# gluecksrad.net
KiCad netlist of a schematic drawn in EAGLE
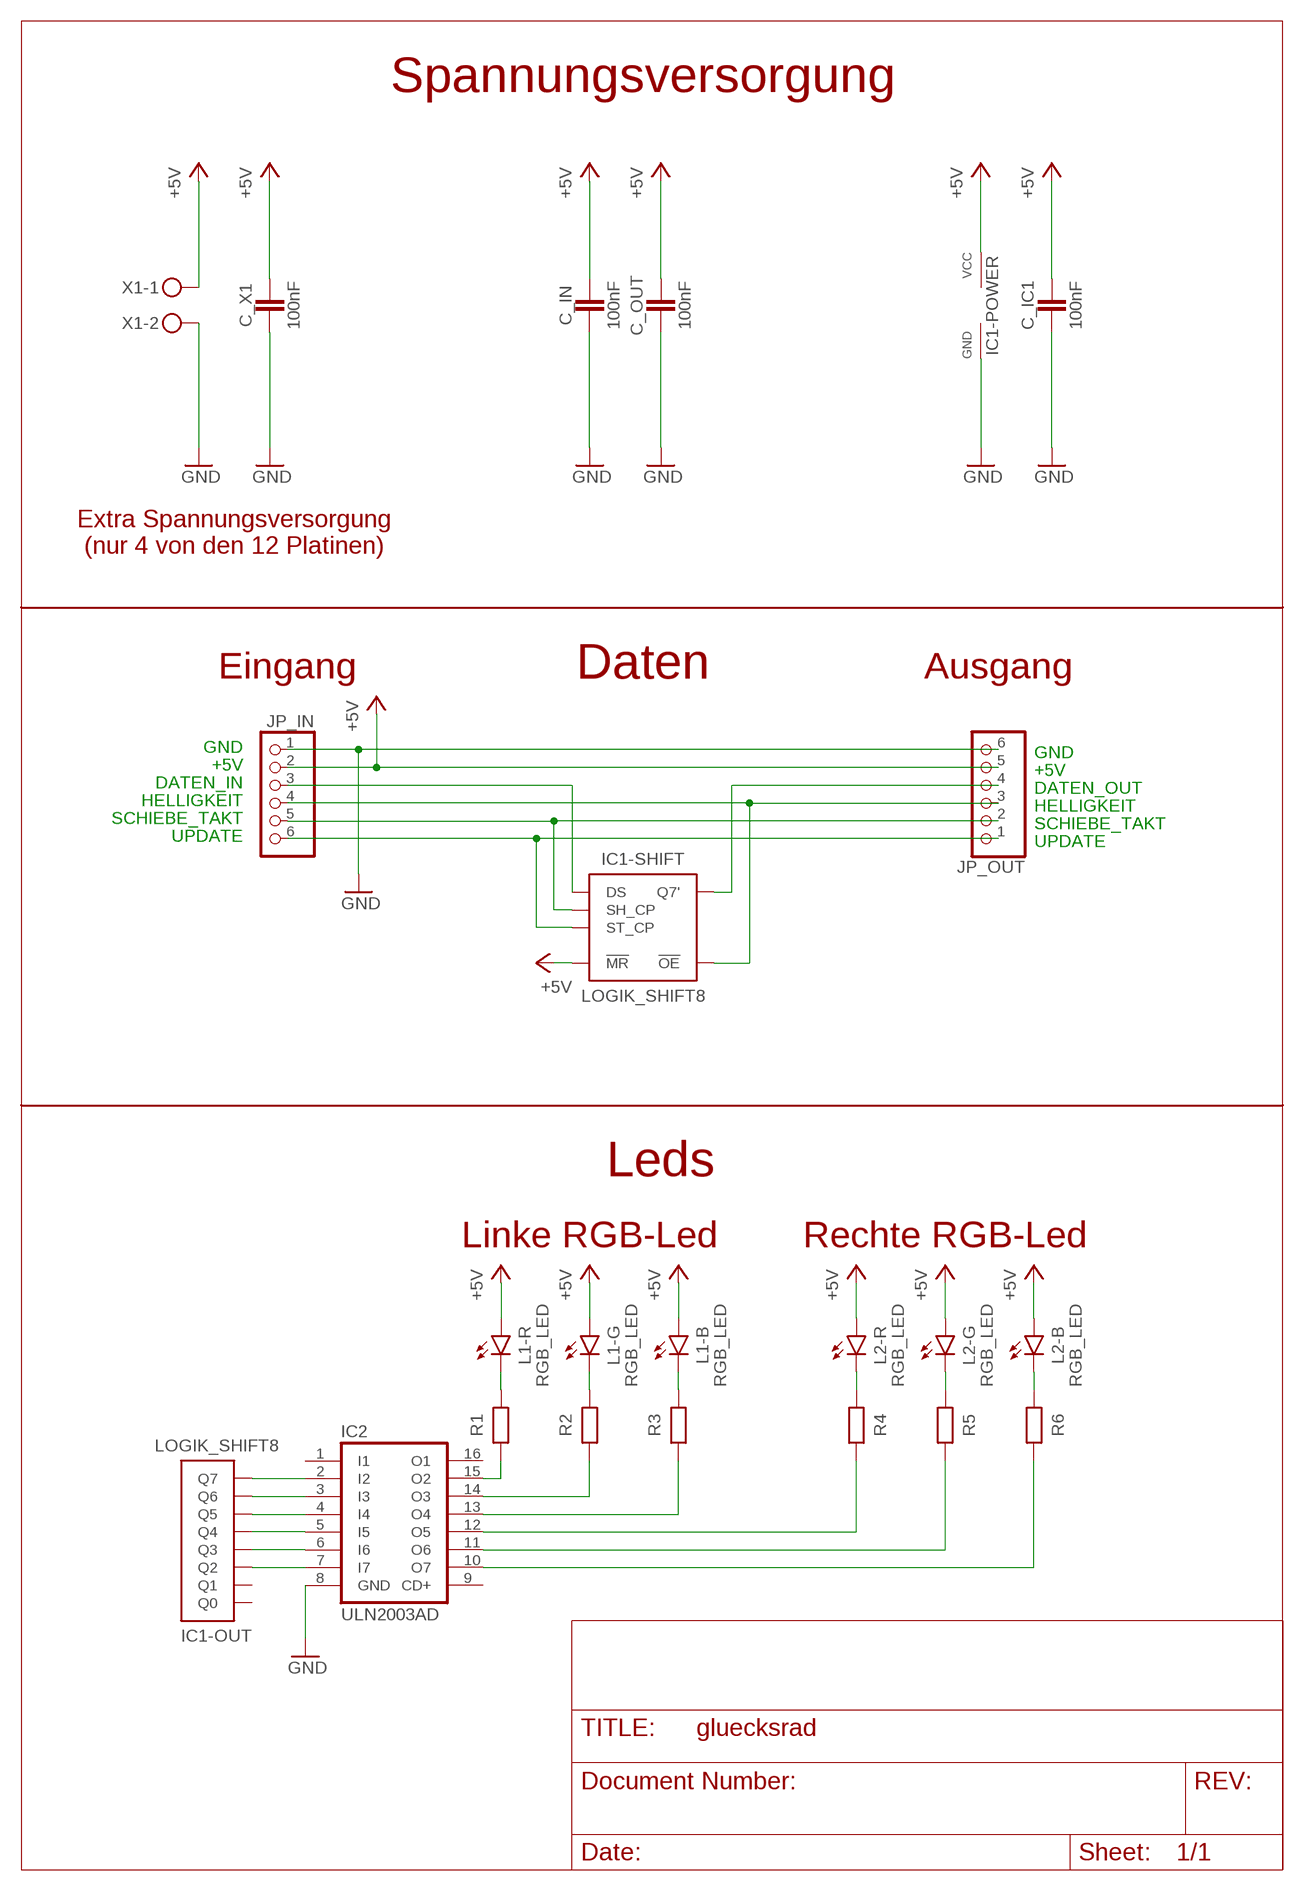
[diagram p0: schematic, sheet 1]

(export (version "E")
  (design (tool "Eeschema 10.0.6"))
  (components
    (comp (ref "C_IC1")
      (value "100nF")
      (footprint "eagle-import:C_THT_2")
      (libsource (lib "eagle-import") (part "CAPACITATOR-2,5MM"))
    )
    (comp (ref "C_IN")
      (value "100nF")
      (footprint "eagle-import:C_THT_2")
      (libsource (lib "eagle-import") (part "CAPACITATOR-2,5MM"))
    )
    (comp (ref "C_OUT")
      (value "100nF")
      (footprint "eagle-import:C_THT_2")
      (libsource (lib "eagle-import") (part "CAPACITATOR-2,5MM"))
    )
    (comp (ref "C_X1")
      (value "100nF")
      (footprint "eagle-import:C_THT_2")
      (libsource (lib "eagle-import") (part "CAPACITATOR-2,5MM"))
    )
    (comp (ref "IC1")
      (value "LOGIK_SHIFT8")
      (footprint "eagle-import:IC_SOIC16")
      (libsource (lib "eagle-import") (part "LOGIK_SHIFT8"))
    )
    (comp (ref "IC2")
      (value "ULN2003AD")
      (footprint "eagle-import:SO16")
      (libsource (lib "eagle-import") (part "ULN2003AD"))
    )
    (comp (ref "JP_IN")
      (value "PINHD-1X6/90")
      (footprint "eagle-import:1X06_90")
      (libsource (lib "eagle-import") (part "PINHD-1X6/90"))
    )
    (comp (ref "JP_OUT")
      (value "PINHD-1X6/90")
      (footprint "eagle-import:1X06_90")
      (libsource (lib "eagle-import") (part "PINHD-1X6/90"))
    )
    (comp (ref "L1")
      (value "RGB_LED")
      (footprint "eagle-import:LED_TOP_PLCC6")
      (libsource (lib "eagle-import") (part "LED_3X"))
    )
    (comp (ref "L2")
      (value "RGB_LED")
      (footprint "eagle-import:LED_TOP_PLCC6")
      (libsource (lib "eagle-import") (part "LED_3X"))
    )
    (comp (ref "R1")
      (value "RESISTOR-10MM")
      (footprint "eagle-import:R_THT_4")
      (libsource (lib "eagle-import") (part "RESISTOR-10MM"))
    )
    (comp (ref "R2")
      (value "RESISTOR-10MM")
      (footprint "eagle-import:R_THT_4")
      (libsource (lib "eagle-import") (part "RESISTOR-10MM"))
    )
    (comp (ref "R3")
      (value "RESISTOR-10MM")
      (footprint "eagle-import:R_THT_4")
      (libsource (lib "eagle-import") (part "RESISTOR-10MM"))
    )
    (comp (ref "R4")
      (value "RESISTOR-10MM")
      (footprint "eagle-import:R_THT_4")
      (libsource (lib "eagle-import") (part "RESISTOR-10MM"))
    )
    (comp (ref "R5")
      (value "RESISTOR-10MM")
      (footprint "eagle-import:R_THT_4")
      (libsource (lib "eagle-import") (part "RESISTOR-10MM"))
    )
    (comp (ref "R6")
      (value "RESISTOR-10MM")
      (footprint "eagle-import:R_THT_4")
      (libsource (lib "eagle-import") (part "RESISTOR-10MM"))
    )
    (comp (ref "X1")
      (value "STECKER_SPG_2")
      (footprint "eagle-import:STECKER_SPG_2")
      (libsource (lib "eagle-import") (part "STECKER_SPG_2"))
    )
  )
  (nets
    (net (code "1") (name "+5V") (class "Default")
      (node (ref "C_IC1") (pin "1") (pinfunction "1_1") (pintype "passive"))
      (node (ref "C_IN") (pin "1") (pinfunction "1_1") (pintype "passive"))
      (node (ref "C_OUT") (pin "1") (pinfunction "1_1") (pintype "passive"))
      (node (ref "C_X1") (pin "1") (pinfunction "1_1") (pintype "passive"))
      (node (ref "IC1") (pin "P$10") (pinfunction "~{MR}_P$10") (pintype "input"))
      (node (ref "IC1") (pin "P$16") (pinfunction "VCC_P$16") (pintype "power_in"))
      (node (ref "JP_IN") (pin "2") (pinfunction "2_2") (pintype "passive"))
      (node (ref "JP_OUT") (pin "5") (pinfunction "5_5") (pintype "passive"))
      (node (ref "L1") (pin "1") (pinfunction "A_1") (pintype "passive"))
      (node (ref "L1") (pin "3") (pinfunction "A_3") (pintype "passive"))
      (node (ref "L1") (pin "4") (pinfunction "A_4") (pintype "passive"))
      (node (ref "L2") (pin "1") (pinfunction "A_1") (pintype "passive"))
      (node (ref "L2") (pin "3") (pinfunction "A_3") (pintype "passive"))
      (node (ref "L2") (pin "4") (pinfunction "A_4") (pintype "passive"))
      (node (ref "X1") (pin "1") (pinfunction "KL_1") (pintype "passive"))
    )
    (net (code "2") (name "/DATEN_IN") (class "Default")
      (node (ref "IC1") (pin "P$14") (pinfunction "DS_P$14") (pintype "input"))
      (node (ref "JP_IN") (pin "3") (pinfunction "3_3") (pintype "passive"))
    )
    (net (code "3") (name "/DATEN_OUT") (class "Default")
      (node (ref "IC1") (pin "P$9") (pinfunction "Q7'_P$9") (pintype "output"))
      (node (ref "JP_OUT") (pin "4") (pinfunction "4_4") (pintype "passive"))
    )
    (net (code "4") (name "/HELLIGKEIT") (class "Default")
      (node (ref "IC1") (pin "P$13") (pinfunction "~{OE}_P$13") (pintype "input"))
      (node (ref "JP_IN") (pin "4") (pinfunction "4_4") (pintype "passive"))
      (node (ref "JP_OUT") (pin "3") (pinfunction "3_3") (pintype "passive"))
    )
    (net (code "5") (name "/SCHIEBE_TAKT") (class "Default")
      (node (ref "IC1") (pin "P$11") (pinfunction "SH_CP_P$11") (pintype "input"))
      (node (ref "JP_IN") (pin "5") (pinfunction "5_5") (pintype "passive"))
      (node (ref "JP_OUT") (pin "2") (pinfunction "2_2") (pintype "passive"))
    )
    (net (code "6") (name "/UPDATE") (class "Default")
      (node (ref "IC1") (pin "P$12") (pinfunction "ST_CP_P$12") (pintype "input"))
      (node (ref "JP_IN") (pin "6") (pinfunction "6_6") (pintype "passive"))
      (node (ref "JP_OUT") (pin "1") (pinfunction "1_1") (pintype "passive"))
    )
    (net (code "7") (name "GND") (class "Default")
      (node (ref "C_IC1") (pin "2") (pinfunction "2_2") (pintype "passive"))
      (node (ref "C_IN") (pin "2") (pinfunction "2_2") (pintype "passive"))
      (node (ref "C_OUT") (pin "2") (pinfunction "2_2") (pintype "passive"))
      (node (ref "C_X1") (pin "2") (pinfunction "2_2") (pintype "passive"))
      (node (ref "IC1") (pin "P$8") (pinfunction "GND_P$8") (pintype "power_in"))
      (node (ref "IC2") (pin "8") (pinfunction "GND_8") (pintype "power_in"))
      (node (ref "JP_IN") (pin "1") (pinfunction "1_1") (pintype "passive"))
      (node (ref "JP_OUT") (pin "6") (pinfunction "6_6") (pintype "passive"))
      (node (ref "X1") (pin "2") (pinfunction "KL_2") (pintype "passive"))
    )
    (net (code "8") (name "Net-(IC1A-Q2)") (class "Default")
      (node (ref "IC1") (pin "P$2") (pinfunction "Q2_P$2") (pintype "output"))
      (node (ref "IC2") (pin "7") (pinfunction "I7_7") (pintype "input"))
    )
    (net (code "9") (name "Net-(IC1A-Q3)") (class "Default")
      (node (ref "IC1") (pin "P$3") (pinfunction "Q3_P$3") (pintype "output"))
      (node (ref "IC2") (pin "6") (pinfunction "I6_6") (pintype "input"))
    )
    (net (code "10") (name "Net-(IC1A-Q4)") (class "Default")
      (node (ref "IC1") (pin "P$4") (pinfunction "Q4_P$4") (pintype "output"))
      (node (ref "IC2") (pin "5") (pinfunction "I5_5") (pintype "input"))
    )
    (net (code "11") (name "Net-(IC1A-Q5)") (class "Default")
      (node (ref "IC1") (pin "P$5") (pinfunction "Q5_P$5") (pintype "output"))
      (node (ref "IC2") (pin "4") (pinfunction "I4_4") (pintype "input"))
    )
    (net (code "12") (name "Net-(IC1A-Q6)") (class "Default")
      (node (ref "IC1") (pin "P$6") (pinfunction "Q6_P$6") (pintype "output"))
      (node (ref "IC2") (pin "3") (pinfunction "I3_3") (pintype "input"))
    )
    (net (code "13") (name "Net-(IC1A-Q7)") (class "Default")
      (node (ref "IC1") (pin "P$7") (pinfunction "Q7_P$7") (pintype "output"))
      (node (ref "IC2") (pin "2") (pinfunction "I2_2") (pintype "input"))
    )
    (net (code "14") (name "Net-(IC2-O2)") (class "Default")
      (node (ref "IC2") (pin "15") (pinfunction "O2_15") (pintype "open_collector"))
      (node (ref "R1") (pin "2") (pinfunction "P2_2") (pintype "passive"))
    )
    (net (code "15") (name "Net-(IC2-O3)") (class "Default")
      (node (ref "IC2") (pin "14") (pinfunction "O3_14") (pintype "open_collector"))
      (node (ref "R2") (pin "2") (pinfunction "P2_2") (pintype "passive"))
    )
    (net (code "16") (name "Net-(IC2-O4)") (class "Default")
      (node (ref "IC2") (pin "13") (pinfunction "O4_13") (pintype "open_collector"))
      (node (ref "R3") (pin "2") (pinfunction "P2_2") (pintype "passive"))
    )
    (net (code "17") (name "Net-(IC2-O5)") (class "Default")
      (node (ref "IC2") (pin "12") (pinfunction "O5_12") (pintype "open_collector"))
      (node (ref "R4") (pin "1") (pinfunction "P1_1") (pintype "passive"))
    )
    (net (code "18") (name "Net-(IC2-O6)") (class "Default")
      (node (ref "IC2") (pin "11") (pinfunction "O6_11") (pintype "open_collector"))
      (node (ref "R5") (pin "1") (pinfunction "P1_1") (pintype "passive"))
    )
    (net (code "19") (name "Net-(IC2-O7)") (class "Default")
      (node (ref "IC2") (pin "10") (pinfunction "O7_10") (pintype "open_collector"))
      (node (ref "R6") (pin "1") (pinfunction "P1_1") (pintype "passive"))
    )
    (net (code "20") (name "Net-(L1A-C)") (class "Default")
      (node (ref "L1") (pin "5") (pinfunction "C_5") (pintype "passive"))
      (node (ref "R3") (pin "1") (pinfunction "P1_1") (pintype "passive"))
    )
    (net (code "21") (name "Net-(L1B-C)") (class "Default")
      (node (ref "L1") (pin "2") (pinfunction "C_2") (pintype "passive"))
      (node (ref "R2") (pin "1") (pinfunction "P1_1") (pintype "passive"))
    )
    (net (code "22") (name "Net-(L1C-C)") (class "Default")
      (node (ref "L1") (pin "6") (pinfunction "C_6") (pintype "passive"))
      (node (ref "R1") (pin "1") (pinfunction "P1_1") (pintype "passive"))
    )
    (net (code "23") (name "Net-(L2A-C)") (class "Default")
      (node (ref "L2") (pin "5") (pinfunction "C_5") (pintype "passive"))
      (node (ref "R6") (pin "2") (pinfunction "P2_2") (pintype "passive"))
    )
    (net (code "24") (name "Net-(L2B-C)") (class "Default")
      (node (ref "L2") (pin "2") (pinfunction "C_2") (pintype "passive"))
      (node (ref "R5") (pin "2") (pinfunction "P2_2") (pintype "passive"))
    )
    (net (code "25") (name "Net-(L2C-C)") (class "Default")
      (node (ref "L2") (pin "6") (pinfunction "C_6") (pintype "passive"))
      (node (ref "R4") (pin "2") (pinfunction "P2_2") (pintype "passive"))
    )
    (net (code "26") (name "unconnected-(IC1A-Q0-PadP$15)") (class "Default")
      (node (ref "IC1") (pin "P$15") (pinfunction "Q0_P$15") (pintype "output"))
    )
    (net (code "27") (name "unconnected-(IC1A-Q1-PadP$1)") (class "Default")
      (node (ref "IC1") (pin "P$1") (pinfunction "Q1_P$1") (pintype "output"))
    )
    (net (code "28") (name "unconnected-(IC2-CD+-Pad9)") (class "Default")
      (node (ref "IC2") (pin "9") (pinfunction "CD+_9") (pintype "passive"))
    )
    (net (code "29") (name "unconnected-(IC2-I1-Pad1)") (class "Default")
      (node (ref "IC2") (pin "1") (pinfunction "I1_1") (pintype "input"))
    )
    (net (code "30") (name "unconnected-(IC2-O1-Pad16)") (class "Default")
      (node (ref "IC2") (pin "16") (pinfunction "O1_16") (pintype "open_collector"))
    )
  )
)
